# Digispark_clone.net
KiCad netlist of a schematic drawn in EAGLE
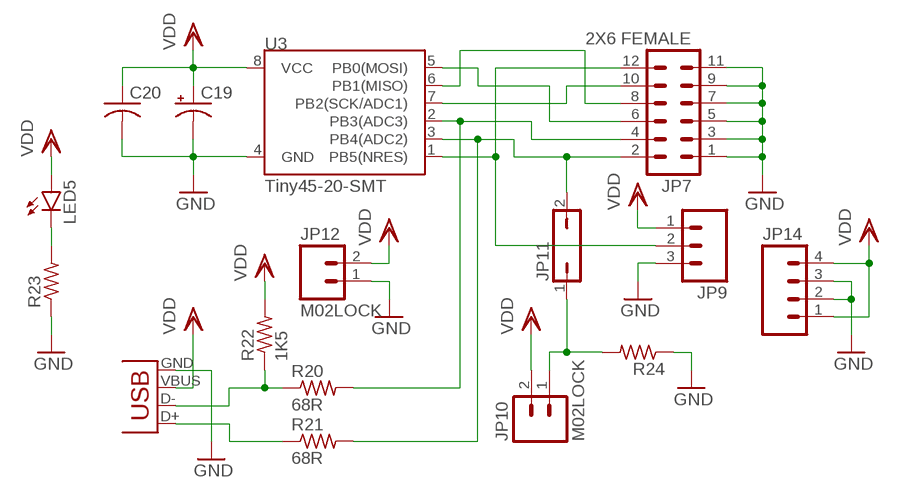
[diagram p0: schematic, sheet 1]

(export (version "E")
  (design (tool "Eeschema 10.0.6"))
  (components
    (comp (ref "C19")
      (value "CPOL-USE2-5")
      (footprint "eagle-import:E2-5")
      (libsource (lib "eagle-import") (part "CPOL-USE2-5"))
    )
    (comp (ref "C20")
      (value "C-USC0805")
      (footprint "eagle-import:C0805")
      (libsource (lib "eagle-import") (part "C-USC0805"))
    )
    (comp (ref "JP7")
      (value "2X6 FEMALE")
      (footprint "eagle-import:2X6")
      (libsource (lib "eagle-import") (part "M06X2PTH_FEMALE"))
    )
    (comp (ref "JP8")
      (value "USB-SMD-NS")
      (footprint "eagle-import:USB-MINIB-NOSTOP")
      (libsource (lib "eagle-import") (part "USB-SMD-NS"))
    )
    (comp (ref "JP9")
      (value "M03LOCK")
      (footprint "eagle-import:1X03_LOCK")
      (libsource (lib "eagle-import") (part "M03LOCK"))
    )
    (comp (ref "JP10")
      (value "M02LOCK")
      (footprint "eagle-import:1X02_LOCK")
      (libsource (lib "eagle-import") (part "M02LOCK"))
    )
    (comp (ref "JP11")
      (value "JP1Q")
      (footprint "eagle-import:JP1")
      (libsource (lib "eagle-import") (part "JP1Q"))
    )
    (comp (ref "JP12")
      (value "M02LOCK")
      (footprint "eagle-import:1X02_LOCK")
      (libsource (lib "eagle-import") (part "M02LOCK"))
    )
    (comp (ref "JP14")
      (value "M04LOCK")
      (footprint "eagle-import:1X04_LOCK")
      (libsource (lib "eagle-import") (part "M04LOCK"))
    )
    (comp (ref "LED5")
      (value "LED1206")
      (footprint "eagle-import:LED-1206")
      (libsource (lib "eagle-import") (part "LED1206"))
    )
    (comp (ref "R20")
      (value "68R")
      (footprint "eagle-import:R0805")
      (libsource (lib "eagle-import") (part "R-US_R0805"))
    )
    (comp (ref "R21")
      (value "68R")
      (footprint "eagle-import:R0805")
      (libsource (lib "eagle-import") (part "R-US_R0805"))
    )
    (comp (ref "R22")
      (value "1K5")
      (footprint "eagle-import:R0805")
      (libsource (lib "eagle-import") (part "R-US_R0805"))
    )
    (comp (ref "R23")
      (value "R-US_R0805")
      (footprint "eagle-import:R0805")
      (libsource (lib "eagle-import") (part "R-US_R0805"))
    )
    (comp (ref "R24")
      (value "R-US_R0805")
      (footprint "eagle-import:R0805")
      (libsource (lib "eagle-import") (part "R-US_R0805"))
    )
    (comp (ref "U3")
      (value "Tiny45-20-SMT")
      (footprint "eagle-import:SO08-EIAJ")
      (libsource (lib "eagle-import") (part "ATTINY45TINY45-20-SMT"))
    )
  )
  (nets
    (net (code "1") (name "GND") (class "Default")
      (node (ref "C19") (pin "-") (pinfunction "-_-") (pintype "passive"))
      (node (ref "C20") (pin "2") (pinfunction "2_2") (pintype "passive"))
      (node (ref "JP12") (pin "1") (pinfunction "1_1") (pintype "passive"))
      (node (ref "JP14") (pin "2") (pinfunction "2_2") (pintype "passive"))
      (node (ref "JP14") (pin "3") (pinfunction "3_3") (pintype "passive"))
      (node (ref "JP7") (pin "1") (pinfunction "1_1") (pintype "passive"))
      (node (ref "JP7") (pin "11") (pinfunction "11_11") (pintype "passive"))
      (node (ref "JP7") (pin "3") (pinfunction "3_3") (pintype "passive"))
      (node (ref "JP7") (pin "5") (pinfunction "5_5") (pintype "passive"))
      (node (ref "JP7") (pin "7") (pinfunction "7_7") (pintype "passive"))
      (node (ref "JP7") (pin "9") (pinfunction "9_9") (pintype "passive"))
      (node (ref "JP8") (pin "GND") (pinfunction "GND_GND") (pintype "bidirectional"))
      (node (ref "JP9") (pin "3") (pinfunction "3_3") (pintype "passive"))
      (node (ref "R23") (pin "1") (pinfunction "1_1") (pintype "passive"))
      (node (ref "R24") (pin "1") (pinfunction "1_1") (pintype "passive"))
      (node (ref "U3") (pin "4") (pinfunction "GND_4") (pintype "bidirectional"))
    )
    (net (code "2") (name "Net-(JP8-PadD+)") (class "Default")
      (node (ref "JP8") (pin "D+") (pinfunction "D+_D+") (pintype "bidirectional"))
      (node (ref "R21") (pin "1") (pinfunction "1_1") (pintype "passive"))
    )
    (net (code "3") (name "Net-(JP8-PadD-)") (class "Default")
      (node (ref "JP8") (pin "D-") (pinfunction "D-_D-") (pintype "bidirectional"))
      (node (ref "R20") (pin "1") (pinfunction "1_1") (pintype "passive"))
      (node (ref "R22") (pin "1") (pinfunction "1_1") (pintype "passive"))
    )
    (net (code "4") (name "Net-(JP10-Pad1)") (class "Default")
      (node (ref "JP10") (pin "1") (pinfunction "1_1") (pintype "passive"))
      (node (ref "JP11") (pin "1") (pinfunction "1_1") (pintype "passive"))
      (node (ref "R24") (pin "2") (pinfunction "2_2") (pintype "passive"))
    )
    (net (code "5") (name "Net-(LED5-PadC)") (class "Default")
      (node (ref "LED5") (pin "C") (pinfunction "C_C") (pintype "passive"))
      (node (ref "R23") (pin "2") (pinfunction "2_2") (pintype "passive"))
    )
    (net (code "6") (name "Net-(U3-PB0(MOSI))") (class "Default")
      (node (ref "JP7") (pin "6") (pinfunction "6_6") (pintype "passive"))
      (node (ref "U3") (pin "5") (pinfunction "PB0(MOSI)_5") (pintype "bidirectional"))
    )
    (net (code "7") (name "Net-(U3-PB1(MISO))") (class "Default")
      (node (ref "JP7") (pin "8") (pinfunction "8_8") (pintype "passive"))
      (node (ref "U3") (pin "6") (pinfunction "PB1(MISO)_6") (pintype "bidirectional"))
    )
    (net (code "8") (name "Net-(U3-PB2(SCK{slash}ADC1))") (class "Default")
      (node (ref "JP7") (pin "10") (pinfunction "10_10") (pintype "passive"))
      (node (ref "U3") (pin "7") (pinfunction "PB2(SCK/ADC1)_7") (pintype "bidirectional"))
    )
    (net (code "9") (name "Net-(U3-PB3(ADC3))") (class "Default")
      (node (ref "JP7") (pin "4") (pinfunction "4_4") (pintype "passive"))
      (node (ref "R20") (pin "2") (pinfunction "2_2") (pintype "passive"))
      (node (ref "U3") (pin "2") (pinfunction "PB3(ADC3)_2") (pintype "bidirectional"))
    )
    (net (code "10") (name "Net-(U3-PB4(ADC2))") (class "Default")
      (node (ref "JP11") (pin "2") (pinfunction "2_2") (pintype "passive"))
      (node (ref "JP7") (pin "2") (pinfunction "2_2") (pintype "passive"))
      (node (ref "R21") (pin "2") (pinfunction "2_2") (pintype "passive"))
      (node (ref "U3") (pin "3") (pinfunction "PB4(ADC2)_3") (pintype "bidirectional"))
    )
    (net (code "11") (name "Net-(U3-PB5(NRES))") (class "Default")
      (node (ref "JP7") (pin "12") (pinfunction "12_12") (pintype "passive"))
      (node (ref "JP9") (pin "2") (pinfunction "2_2") (pintype "passive"))
      (node (ref "U3") (pin "1") (pinfunction "PB5(NRES)_1") (pintype "bidirectional"))
    )
    (net (code "12") (name "VDD") (class "Default")
      (node (ref "C19") (pin "+") (pinfunction "+_+") (pintype "passive"))
      (node (ref "C20") (pin "1") (pinfunction "1_1") (pintype "passive"))
      (node (ref "JP10") (pin "2") (pinfunction "2_2") (pintype "passive"))
      (node (ref "JP12") (pin "2") (pinfunction "2_2") (pintype "passive"))
      (node (ref "JP14") (pin "1") (pinfunction "1_1") (pintype "passive"))
      (node (ref "JP14") (pin "4") (pinfunction "4_4") (pintype "passive"))
      (node (ref "JP8") (pin "VBUS") (pinfunction "VBUS_VBUS") (pintype "bidirectional"))
      (node (ref "JP9") (pin "1") (pinfunction "1_1") (pintype "passive"))
      (node (ref "LED5") (pin "A") (pinfunction "A_A") (pintype "passive"))
      (node (ref "R22") (pin "2") (pinfunction "2_2") (pintype "passive"))
      (node (ref "U3") (pin "8") (pinfunction "VCC_8") (pintype "bidirectional"))
    )
  )
)
